# 555_timer_schematic.net
KiCad netlist of a schematic drawn in Altium Designer
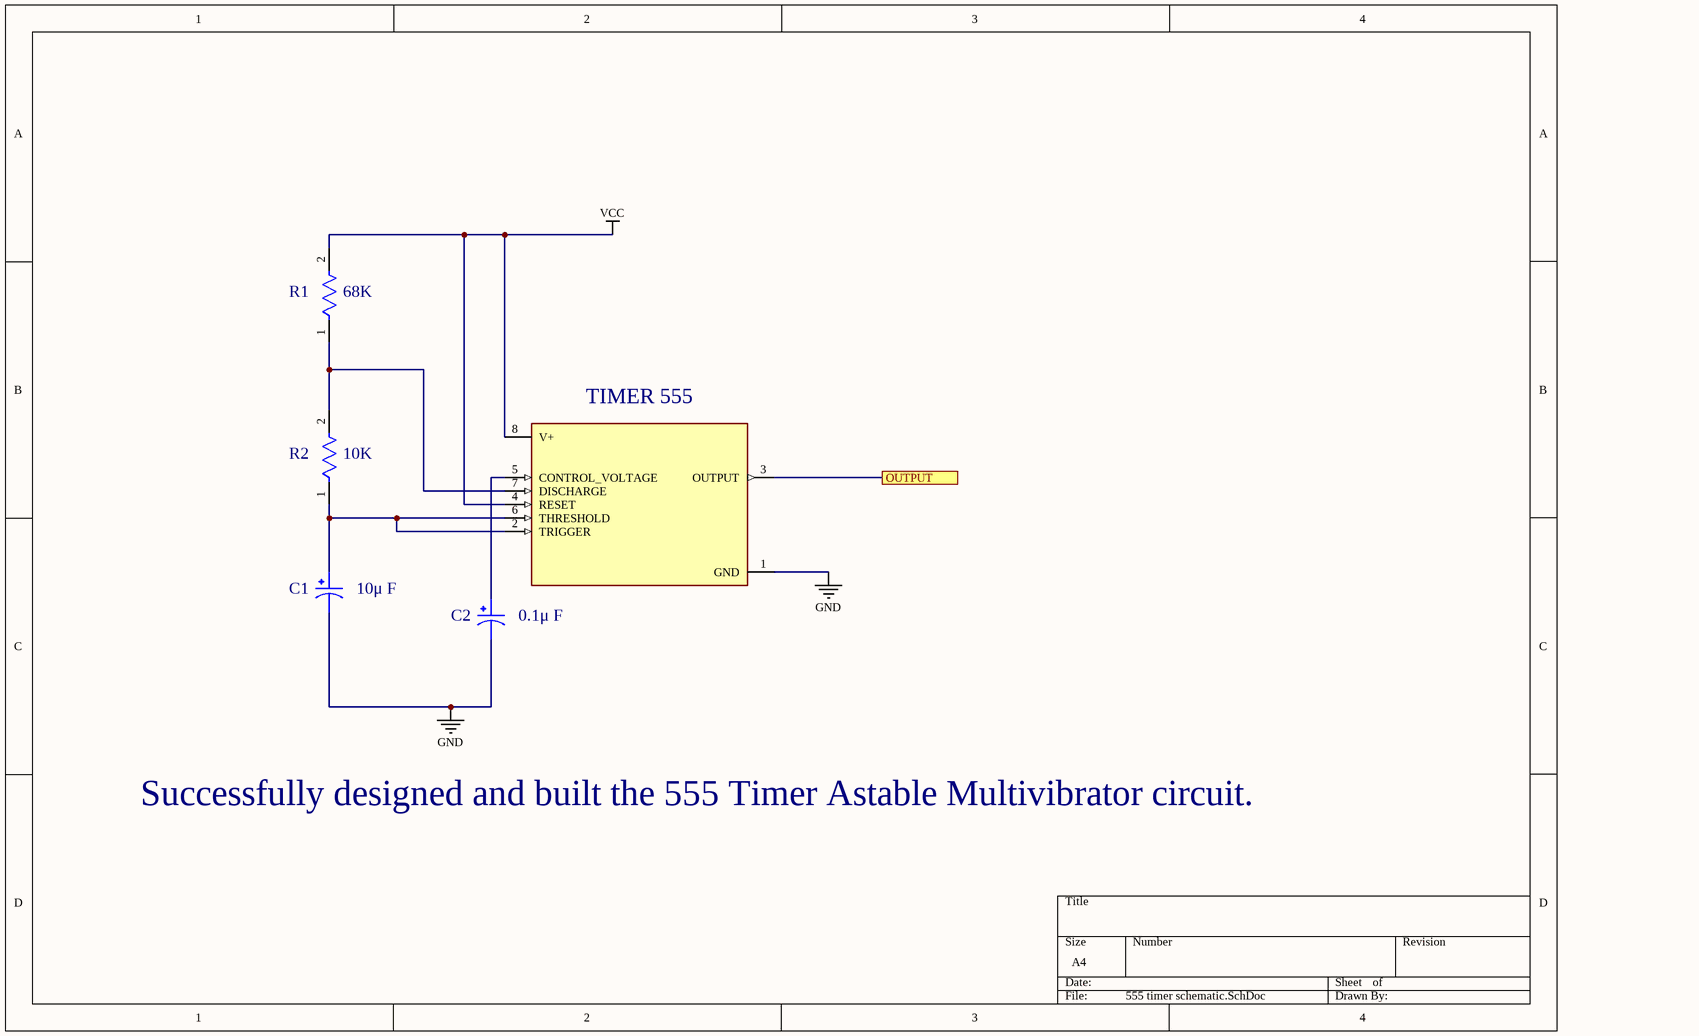
[diagram p0: 555 timer schematic.SchDoc]

(export (version "E")
  (design (tool "Eeschema 10.0.6"))
  (components
    (comp (ref "C1")
      (value "10μ F")
      (footprint "CAPPRD500W60D1330H2700")
      (description "4700 ÂµF 10 V Aluminum Electrolytic Capacitors Radial, Can 98.8mOhm @ 120Hz 2000 Hrs @ 85Â°C")
      (fields (field (name "MF") "Illinois Capacitor") (field (name "MP") "478CKS010M"))
      (libsource (lib "478CKS010M") (part "478CKS010M"))
    )
    (comp (ref "C2")
      (value "0.1μ F")
      (footprint "CAPPRD500W60D1330H2700")
      (description "4700 ÂµF 10 V Aluminum Electrolytic Capacitors Radial, Can 98.8mOhm @ 120Hz 2000 Hrs @ 85Â°C")
      (fields (field (name "MF") "Illinois Capacitor") (field (name "MP") "478CKS010M"))
      (libsource (lib "478CKS010M") (part "478CKS010M"))
    )
    (comp (ref "R1")
      (value "68K")
      (footprint "FP-MFR-25-MFG")
      (description "RES 1.18K OHM 1/4W 1% AXIAL")
      (fields (field (name "MANUFACTURER") "Yageo") (field (name "TOLERANCE") "1%"))
      (libsource (lib "RESISTOR NEW") (part "CMP-03413-000001-1"))
    )
    (comp (ref "R2")
      (value "10K")
      (footprint "FP-MFR-25-MFG")
      (description "RES 1.18K OHM 1/4W 1% AXIAL")
      (fields (field (name "MANUFACTURER") "Yageo") (field (name "TOLERANCE") "1%"))
      (libsource (lib "RESISTOR NEW") (part "CMP-03413-000001-1"))
    )
    (comp (ref "TIMER 555")
      (value "LM555CN/NOPB")
      (footprint "DIP794W45P254L959H508Q8")
      (description "Highly Stable 555 Timer")
      (fields (field (name "MF") "Texas Instruments"))
      (libsource (lib "LM555CN_NOPB (1)") (part "LM555CN/NOPB"))
    )
  )
  (nets
    (net (code "1") (name "/OUTPUT") (class "Default")
      (node (ref "TIMER 555") (pin "3") (pinfunction "OUTPUT_3") (pintype "output"))
    )
    (net (code "2") (name "GND") (class "Default")
      (node (ref "C1") (pin "2") (pinfunction "2_2") (pintype "passive"))
      (node (ref "C2") (pin "2") (pinfunction "2_2") (pintype "passive"))
      (node (ref "TIMER 555") (pin "1") (pinfunction "GND_1") (pintype "power_in"))
    )
    (net (code "3") (name "Net-(TIMER 555-CONTROL_VOLTAGE)") (class "Default")
      (node (ref "C2") (pin "1") (pinfunction "1_1") (pintype "passive"))
      (node (ref "TIMER 555") (pin "5") (pinfunction "CONTROL_VOLTAGE_5") (pintype "input"))
    )
    (net (code "4") (name "Net-(TIMER 555-DISCHARGE)") (class "Default")
      (node (ref "R1") (pin "1") (pinfunction "1_1") (pintype "passive"))
      (node (ref "R2") (pin "2") (pinfunction "2_2") (pintype "passive"))
      (node (ref "TIMER 555") (pin "7") (pinfunction "DISCHARGE_7") (pintype "input"))
    )
    (net (code "5") (name "Net-(TIMER 555-THRESHOLD)") (class "Default")
      (node (ref "C1") (pin "1") (pinfunction "1_1") (pintype "passive"))
      (node (ref "R2") (pin "1") (pinfunction "1_1") (pintype "passive"))
      (node (ref "TIMER 555") (pin "2") (pinfunction "TRIGGER_2") (pintype "input"))
      (node (ref "TIMER 555") (pin "6") (pinfunction "THRESHOLD_6") (pintype "input"))
    )
    (net (code "6") (name "VCC") (class "Default")
      (node (ref "R1") (pin "2") (pinfunction "2_2") (pintype "passive"))
      (node (ref "TIMER 555") (pin "4") (pinfunction "RESET_4") (pintype "input"))
      (node (ref "TIMER 555") (pin "8") (pinfunction "V+_8") (pintype "power_in"))
    )
  )
)
